# piezo-buffer-and-preamp_v0-1.net
KiCad netlist of a schematic drawn in EAGLE
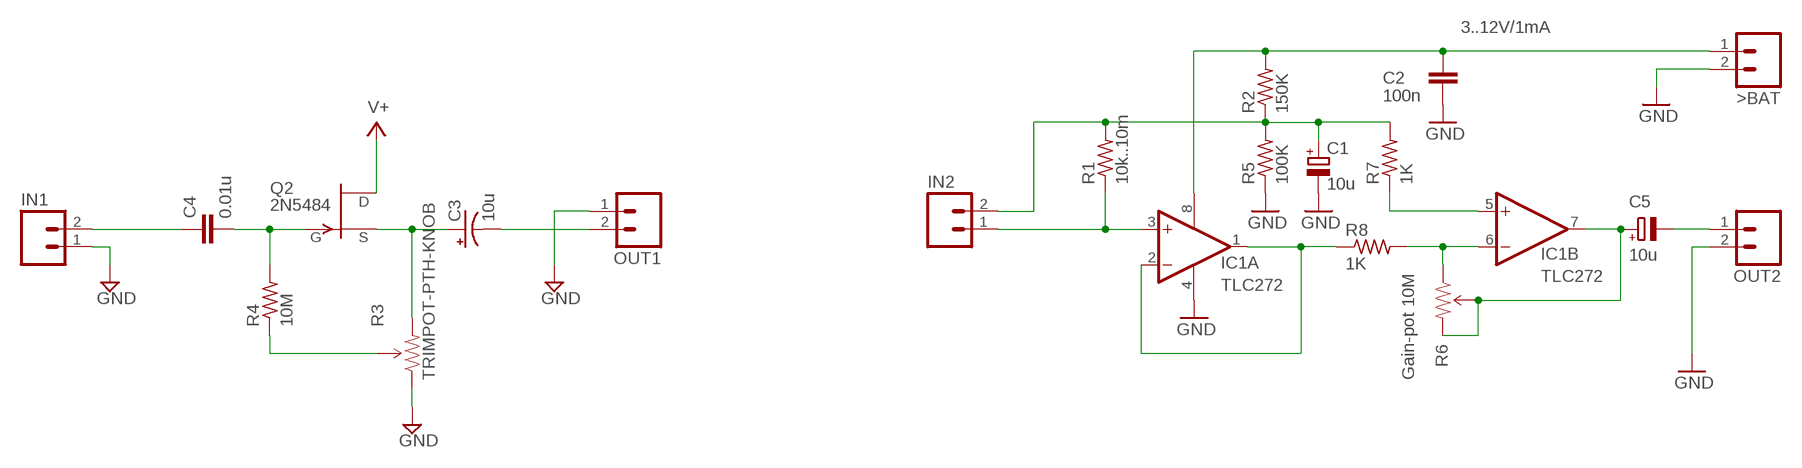
[diagram p0: schematic, sheet 1]

(export (version "E")
  (design (tool "Eeschema 10.0.6"))
  (components
    (comp (ref ">BAT")
      (value "M02LOCK")
      (footprint "eagle-import:1X02_LOCK")
      (libsource (lib "eagle-import") (part "M02LOCK"))
    )
    (comp (ref "C1")
      (value "10u")
      (footprint "eagle-import:E2,5-5")
      (libsource (lib "eagle-import") (part "CPOL-EUE2.5-5"))
    )
    (comp (ref "C2")
      (value "100n")
      (footprint "eagle-import:C025-025X050")
      (libsource (lib "eagle-import") (part "C-EU025-025X050"))
    )
    (comp (ref "C3")
      (value "10u")
      (footprint "eagle-import:CPOL-RADIAL-10UF-25V")
      (libsource (lib "eagle-import") (part "CAP_POLPTH2"))
    )
    (comp (ref "C4")
      (value "0.01u")
      (footprint "eagle-import:C5B3")
      (libsource (lib "eagle-import") (part "C5/3"))
    )
    (comp (ref "C5")
      (value "10u")
      (footprint "eagle-import:E2,5-5")
      (libsource (lib "eagle-import") (part "CPOL-EUE2.5-5"))
    )
    (comp (ref "IC1")
      (value "TLC272")
      (footprint "eagle-import:DIL08")
      (libsource (lib "eagle-import") (part "TLC272P"))
    )
    (comp (ref "IN1")
      (value "M02LOCK")
      (footprint "eagle-import:1X02_LOCK")
      (libsource (lib "eagle-import") (part "M02LOCK"))
    )
    (comp (ref "IN2")
      (value "M02LOCK")
      (footprint "eagle-import:1X02_LOCK")
      (libsource (lib "eagle-import") (part "M02LOCK"))
    )
    (comp (ref "OUT1")
      (value "M02LOCK")
      (footprint "eagle-import:1X02_LOCK")
      (libsource (lib "eagle-import") (part "M02LOCK"))
    )
    (comp (ref "OUT2")
      (value "M02LOCK")
      (footprint "eagle-import:1X02_LOCK")
      (libsource (lib "eagle-import") (part "M02LOCK"))
    )
    (comp (ref "Q2")
      (value "2N5484")
      (footprint "eagle-import:TO92-")
      (libsource (lib "eagle-import") (part "?5482N4"))
    )
    (comp (ref "R1")
      (value "10k..10m")
      (footprint "eagle-import:0204V")
      (libsource (lib "eagle-import") (part "R-US_0204/2V"))
    )
    (comp (ref "R2")
      (value "150K")
      (footprint "eagle-import:0204V")
      (libsource (lib "eagle-import") (part "R-US_0204/2V"))
    )
    (comp (ref "R3")
      (value "TRIMPOT-PTH-KNOB")
      (footprint "eagle-import:3386U")
      (libsource (lib "eagle-import") (part "TRIMPOT-PTH-KNOB"))
    )
    (comp (ref "R4")
      (value "10M")
      (footprint "eagle-import:0204V")
      (libsource (lib "eagle-import") (part "R-US_0204/2V"))
    )
    (comp (ref "R5")
      (value "100K")
      (footprint "eagle-import:0204V")
      (libsource (lib "eagle-import") (part "R-US_0204/2V"))
    )
    (comp (ref "R6")
      (value "Gain-pot 10M")
      (footprint "eagle-import:3386U")
      (libsource (lib "eagle-import") (part "TRIMPOT-PTH-KNOB"))
    )
    (comp (ref "R7")
      (value "1K")
      (footprint "eagle-import:0204V")
      (libsource (lib "eagle-import") (part "R-US_0204/2V"))
    )
    (comp (ref "R8")
      (value "1K")
      (footprint "eagle-import:0204V")
      (libsource (lib "eagle-import") (part "R-US_0204/2V"))
    )
  )
  (nets
    (net (code "1") (name "GND") (class "Default")
      (node (ref ">BAT") (pin "2") (pinfunction "2_2") (pintype "passive"))
      (node (ref "C1") (pin "-") (pinfunction "-_-") (pintype "passive"))
      (node (ref "C2") (pin "1") (pinfunction "1_1") (pintype "passive"))
      (node (ref "IC1") (pin "4") (pinfunction "V-_4") (pintype "power_in"))
      (node (ref "IN1") (pin "1") (pinfunction "1_1") (pintype "passive"))
      (node (ref "OUT1") (pin "1") (pinfunction "1_1") (pintype "passive"))
      (node (ref "OUT2") (pin "2") (pinfunction "2_2") (pintype "passive"))
      (node (ref "R3") (pin "1") (pinfunction "CCW_1") (pintype "passive"))
      (node (ref "R5") (pin "1") (pinfunction "1_1") (pintype "passive"))
    )
    (net (code "2") (name "Net-(C1-Pad+)") (class "Default")
      (node (ref "C1") (pin "+") (pinfunction "+_+") (pintype "passive"))
      (node (ref "IN2") (pin "2") (pinfunction "2_2") (pintype "passive"))
      (node (ref "R1") (pin "2") (pinfunction "2_2") (pintype "passive"))
      (node (ref "R2") (pin "1") (pinfunction "1_1") (pintype "passive"))
      (node (ref "R5") (pin "2") (pinfunction "2_2") (pintype "passive"))
      (node (ref "R7") (pin "2") (pinfunction "2_2") (pintype "passive"))
    )
    (net (code "3") (name "Net-(C3-+)") (class "Default")
      (node (ref "C3") (pin "1") (pinfunction "+_1") (pintype "passive"))
      (node (ref "Q2") (pin "2") (pinfunction "S_2") (pintype "passive"))
      (node (ref "R3") (pin "3") (pinfunction "CW_3") (pintype "passive"))
    )
    (net (code "4") (name "Net-(C3--)") (class "Default")
      (node (ref "C3") (pin "2") (pinfunction "-_2") (pintype "passive"))
      (node (ref "OUT1") (pin "2") (pinfunction "2_2") (pintype "passive"))
    )
    (net (code "5") (name "Net-(C4-Pad1)") (class "Default")
      (node (ref "C4") (pin "1") (pinfunction "1_1") (pintype "passive"))
      (node (ref "IN1") (pin "2") (pinfunction "2_2") (pintype "passive"))
    )
    (net (code "6") (name "Net-(C5-Pad-)") (class "Default")
      (node (ref "C5") (pin "-") (pinfunction "-_-") (pintype "passive"))
      (node (ref "OUT2") (pin "1") (pinfunction "1_1") (pintype "passive"))
    )
    (net (code "7") (name "Net-(IC1A-+IN)") (class "Default")
      (node (ref "IC1") (pin "3") (pinfunction "+IN_3") (pintype "input"))
      (node (ref "IN2") (pin "1") (pinfunction "1_1") (pintype "passive"))
      (node (ref "R1") (pin "1") (pinfunction "1_1") (pintype "passive"))
    )
    (net (code "8") (name "Net-(IC1A--IN)") (class "Default")
      (node (ref "IC1") (pin "1") (pinfunction "OUT_1") (pintype "output"))
      (node (ref "IC1") (pin "2") (pinfunction "-IN_2") (pintype "input"))
      (node (ref "R8") (pin "1") (pinfunction "1_1") (pintype "passive"))
    )
    (net (code "9") (name "Net-(IC1B-+IN)") (class "Default")
      (node (ref "IC1") (pin "5") (pinfunction "+IN_5") (pintype "input"))
      (node (ref "R7") (pin "1") (pinfunction "1_1") (pintype "passive"))
    )
    (net (code "10") (name "Net-(IC1B--IN)") (class "Default")
      (node (ref "IC1") (pin "6") (pinfunction "-IN_6") (pintype "input"))
      (node (ref "R6") (pin "1") (pinfunction "CCW_1") (pintype "passive"))
      (node (ref "R8") (pin "2") (pinfunction "2_2") (pintype "passive"))
    )
    (net (code "11") (name "Net-(IC1B-OUT)") (class "Default")
      (node (ref "C5") (pin "+") (pinfunction "+_+") (pintype "passive"))
      (node (ref "IC1") (pin "7") (pinfunction "OUT_7") (pintype "output"))
      (node (ref "R6") (pin "2") (pinfunction "WIPER_2") (pintype "passive"))
      (node (ref "R6") (pin "3") (pinfunction "CW_3") (pintype "passive"))
    )
    (net (code "12") (name "Net-(IC1C-V+)") (class "Default")
      (node (ref ">BAT") (pin "1") (pinfunction "1_1") (pintype "passive"))
      (node (ref "C2") (pin "2") (pinfunction "2_2") (pintype "passive"))
      (node (ref "IC1") (pin "8") (pinfunction "V+_8") (pintype "power_in"))
      (node (ref "R2") (pin "2") (pinfunction "2_2") (pintype "passive"))
    )
    (net (code "13") (name "Net-(Q2-G)") (class "Default")
      (node (ref "C4") (pin "2") (pinfunction "2_2") (pintype "passive"))
      (node (ref "Q2") (pin "1") (pinfunction "G_1") (pintype "passive"))
      (node (ref "R4") (pin "2") (pinfunction "2_2") (pintype "passive"))
    )
    (net (code "14") (name "Net-(R3-WIPER)") (class "Default")
      (node (ref "R3") (pin "2") (pinfunction "WIPER_2") (pintype "passive"))
      (node (ref "R4") (pin "1") (pinfunction "1_1") (pintype "passive"))
    )
    (net (code "15") (name "V+") (class "Default")
      (node (ref "Q2") (pin "3") (pinfunction "D_3") (pintype "passive"))
    )
  )
)
